# ucontrol.net
KiCad netlist of a schematic drawn in EAGLE
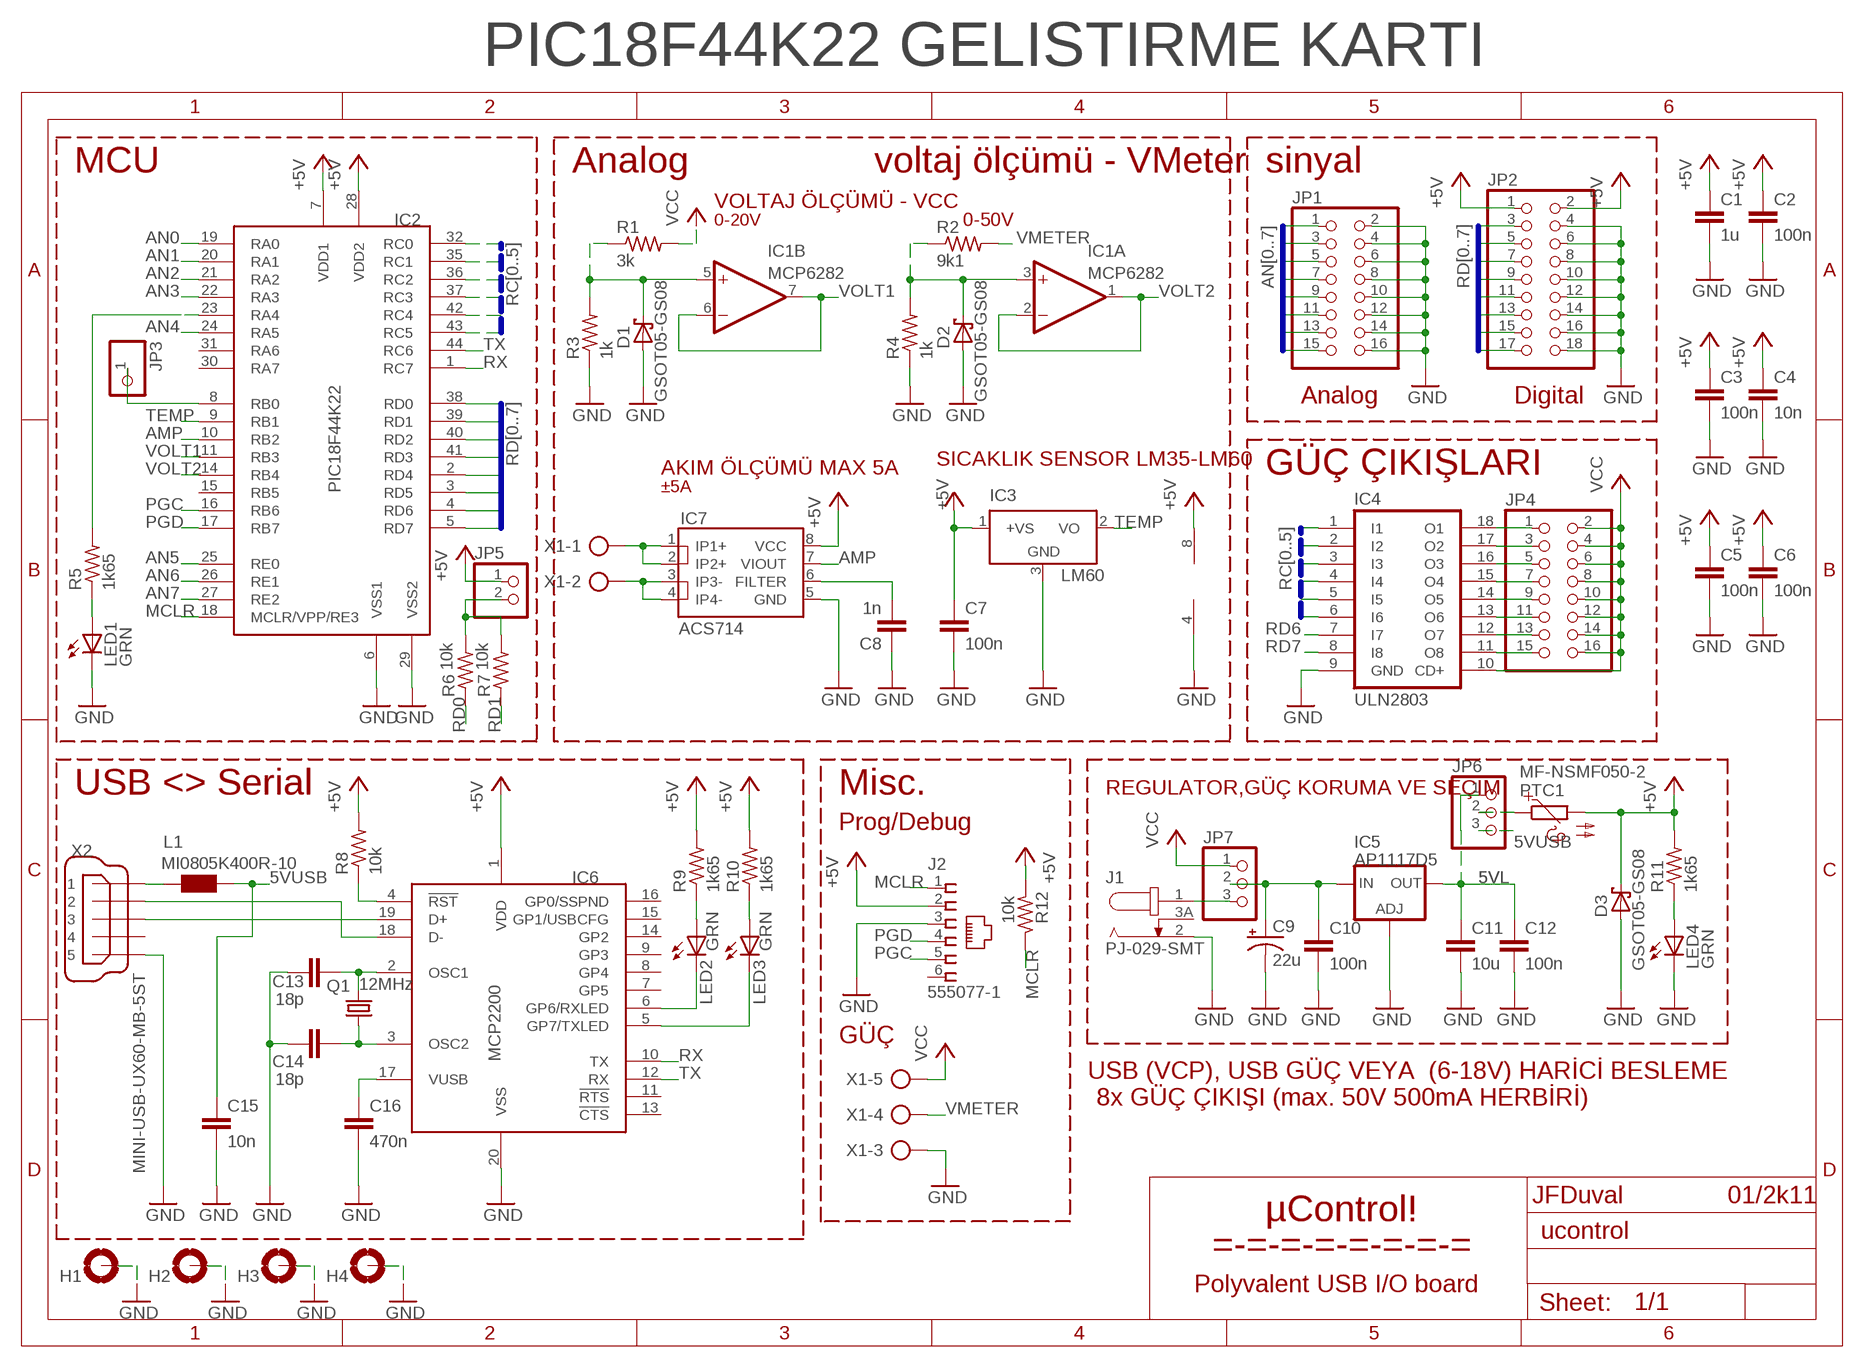
[diagram p0: schematic, sheet 1]

(export (version "E")
  (design (tool "Eeschema 10.0.6"))
  (components
    (comp (ref "C1")
      (value "1u")
      (footprint "eagle-import:C0603")
      (libsource (lib "eagle-import") (part "C-EUC0603"))
    )
    (comp (ref "C2")
      (value "100n")
      (footprint "eagle-import:C0603")
      (libsource (lib "eagle-import") (part "C-EUC0603"))
    )
    (comp (ref "C3")
      (value "100n")
      (footprint "eagle-import:C0603")
      (libsource (lib "eagle-import") (part "C-EUC0603"))
    )
    (comp (ref "C4")
      (value "10n")
      (footprint "eagle-import:C0603")
      (libsource (lib "eagle-import") (part "C-EUC0603"))
    )
    (comp (ref "C5")
      (value "100n")
      (footprint "eagle-import:C0603")
      (libsource (lib "eagle-import") (part "C-EUC0603"))
    )
    (comp (ref "C6")
      (value "100n")
      (footprint "eagle-import:C0603")
      (libsource (lib "eagle-import") (part "C-EUC0603"))
    )
    (comp (ref "C7")
      (value "100n")
      (footprint "eagle-import:C0603")
      (libsource (lib "eagle-import") (part "C-EUC0603"))
    )
    (comp (ref "C8")
      (value "1n")
      (footprint "eagle-import:C0603")
      (libsource (lib "eagle-import") (part "C-EUC0603"))
    )
    (comp (ref "C9")
      (value "22u")
      (footprint "eagle-import:153CLV-0505")
      (libsource (lib "eagle-import") (part "CPOL-US153CLV-0505"))
    )
    (comp (ref "C10")
      (value "100n")
      (footprint "eagle-import:C0603")
      (libsource (lib "eagle-import") (part "C-EUC0603"))
    )
    (comp (ref "C11")
      (value "10u")
      (footprint "eagle-import:C0805")
      (libsource (lib "eagle-import") (part "C-EUC0805"))
    )
    (comp (ref "C12")
      (value "100n")
      (footprint "eagle-import:C0603")
      (libsource (lib "eagle-import") (part "C-EUC0603"))
    )
    (comp (ref "C13")
      (value "18p")
      (footprint "eagle-import:C0603")
      (libsource (lib "eagle-import") (part "C-EUC0603"))
    )
    (comp (ref "C14")
      (value "18p")
      (footprint "eagle-import:C0603")
      (libsource (lib "eagle-import") (part "C-EUC0603"))
    )
    (comp (ref "C15")
      (value "10n")
      (footprint "eagle-import:C0603")
      (libsource (lib "eagle-import") (part "C-EUC0603"))
    )
    (comp (ref "C16")
      (value "470n")
      (footprint "eagle-import:C0603")
      (libsource (lib "eagle-import") (part "C-EUC0603"))
    )
    (comp (ref "D1")
      (value "GSOT05-GS08")
      (footprint "eagle-import:SOT23")
      (libsource (lib "eagle-import") (part "BAS70"))
    )
    (comp (ref "D2")
      (value "GSOT05-GS08")
      (footprint "eagle-import:SOT23")
      (libsource (lib "eagle-import") (part "BAS70"))
    )
    (comp (ref "D3")
      (value "GSOT05-GS08")
      (footprint "eagle-import:SOT23")
      (libsource (lib "eagle-import") (part "BAS70"))
    )
    (comp (ref "H1")
      (value "MOUNT-PAD-ROUND3.2")
      (footprint "eagle-import:3,2-PAD")
      (libsource (lib "eagle-import") (part "MOUNT-PAD-ROUND3.2"))
    )
    (comp (ref "H2")
      (value "MOUNT-PAD-ROUND3.2")
      (footprint "eagle-import:3,2-PAD")
      (libsource (lib "eagle-import") (part "MOUNT-PAD-ROUND3.2"))
    )
    (comp (ref "H3")
      (value "MOUNT-PAD-ROUND3.2")
      (footprint "eagle-import:3,2-PAD")
      (libsource (lib "eagle-import") (part "MOUNT-PAD-ROUND3.2"))
    )
    (comp (ref "H4")
      (value "MOUNT-PAD-ROUND3.2")
      (footprint "eagle-import:3,2-PAD")
      (libsource (lib "eagle-import") (part "MOUNT-PAD-ROUND3.2"))
    )
    (comp (ref "IC1")
      (value "MCP6282")
      (footprint "eagle-import:SO08")
      (libsource (lib "eagle-import") (part "MCP602SN"))
    )
    (comp (ref "IC2")
      (value "PIC18F44K22")
      (footprint "eagle-import:TQFP44")
      (libsource (lib "eagle-import") (part "PIC18F44K22"))
    )
    (comp (ref "IC3")
      (value "LM60")
      (footprint "eagle-import:SOT23")
      (libsource (lib "eagle-import") (part "LM50"))
    )
    (comp (ref "IC4")
      (value "ULN2803")
      (footprint "eagle-import:SO18")
      (libsource (lib "eagle-import") (part "ULN2803"))
    )
    (comp (ref "IC5")
      (value "AP1117D5")
      (footprint "eagle-import:DPACK")
      (libsource (lib "eagle-import") (part "LD117A?DT33TR"))
    )
    (comp (ref "IC6")
      (value "MCP2200")
      (footprint "eagle-import:SSOP20")
      (libsource (lib "eagle-import") (part "MCP2200"))
    )
    (comp (ref "IC7")
      (value "ACS714")
      (footprint "eagle-import:SO08")
      (libsource (lib "eagle-import") (part "ACS712"))
    )
    (comp (ref "J1")
      (value "PJ-029-SMT")
      (footprint "eagle-import:SMT")
      (libsource (lib "eagle-import") (part "PJ-029-SMT"))
    )
    (comp (ref "J2")
      (value "555077-1")
      (footprint "eagle-import:555077-1")
      (libsource (lib "eagle-import") (part "555077-1"))
    )
    (comp (ref "JP1")
      (value "PINHD-2X8")
      (footprint "eagle-import:2X08")
      (libsource (lib "eagle-import") (part "PINHD-2X8"))
    )
    (comp (ref "JP2")
      (value "PINHD-2X9")
      (footprint "eagle-import:2X09")
      (libsource (lib "eagle-import") (part "PINHD-2X9"))
    )
    (comp (ref "JP3")
      (value "PINHD-1X1")
      (footprint "eagle-import:1X01")
      (libsource (lib "eagle-import") (part "PINHD-1X1"))
    )
    (comp (ref "JP4")
      (value "PINHD-2X8")
      (footprint "eagle-import:2X08")
      (libsource (lib "eagle-import") (part "PINHD-2X8"))
    )
    (comp (ref "JP5")
      (value "PINHD-1X2")
      (footprint "eagle-import:1X02")
      (libsource (lib "eagle-import") (part "PINHD-1X2"))
    )
    (comp (ref "JP6")
      (value "PINHD-1X3")
      (footprint "eagle-import:1X03")
      (libsource (lib "eagle-import") (part "PINHD-1X3"))
    )
    (comp (ref "JP7")
      (value "PINHD-1X3")
      (footprint "eagle-import:1X03")
      (libsource (lib "eagle-import") (part "PINHD-1X3"))
    )
    (comp (ref "L1")
      (value "MI0805K400R-10")
      (footprint "eagle-import:0805")
      (libsource (lib "eagle-import") (part "WE-CBF_0805"))
    )
    (comp (ref "LED1")
      (value "GRN")
      (footprint "eagle-import:CHIPLED_0603")
      (libsource (lib "eagle-import") (part "LEDCHIPLED_0603"))
    )
    (comp (ref "LED2")
      (value "GRN")
      (footprint "eagle-import:CHIPLED_0603")
      (libsource (lib "eagle-import") (part "LEDCHIPLED_0603"))
    )
    (comp (ref "LED3")
      (value "GRN")
      (footprint "eagle-import:CHIPLED_0603")
      (libsource (lib "eagle-import") (part "LEDCHIPLED_0603"))
    )
    (comp (ref "LED4")
      (value "GRN")
      (footprint "eagle-import:CHIPLED_0603")
      (libsource (lib "eagle-import") (part "LEDCHIPLED_0603"))
    )
    (comp (ref "PTC1")
      (value "MF-NSMF050-2")
      (footprint "eagle-import:1206")
      (libsource (lib "eagle-import") (part "GENERIC_1206"))
    )
    (comp (ref "Q1")
      (value "12MHz")
      (footprint "eagle-import:HC49UP")
      (libsource (lib "eagle-import") (part "CRYSTALHC49UP"))
    )
    (comp (ref "R1")
      (value "3k")
      (footprint "eagle-import:R0603")
      (libsource (lib "eagle-import") (part "R-US_R0603"))
    )
    (comp (ref "R2")
      (value "9k1")
      (footprint "eagle-import:R0603")
      (libsource (lib "eagle-import") (part "R-US_R0603"))
    )
    (comp (ref "R3")
      (value "1k")
      (footprint "eagle-import:R0603")
      (libsource (lib "eagle-import") (part "R-US_R0603"))
    )
    (comp (ref "R4")
      (value "1k")
      (footprint "eagle-import:R0603")
      (libsource (lib "eagle-import") (part "R-US_R0603"))
    )
    (comp (ref "R5")
      (value "1k65")
      (footprint "eagle-import:R0603")
      (libsource (lib "eagle-import") (part "R-US_R0603"))
    )
    (comp (ref "R6")
      (value "10k")
      (footprint "eagle-import:R0603")
      (libsource (lib "eagle-import") (part "R-US_R0603"))
    )
    (comp (ref "R7")
      (value "10k")
      (footprint "eagle-import:R0603")
      (libsource (lib "eagle-import") (part "R-US_R0603"))
    )
    (comp (ref "R8")
      (value "10k")
      (footprint "eagle-import:R0603")
      (libsource (lib "eagle-import") (part "R-US_R0603"))
    )
    (comp (ref "R9")
      (value "1k65")
      (footprint "eagle-import:R0603")
      (libsource (lib "eagle-import") (part "R-US_R0603"))
    )
    (comp (ref "R10")
      (value "1k65")
      (footprint "eagle-import:R0603")
      (libsource (lib "eagle-import") (part "R-US_R0603"))
    )
    (comp (ref "R11")
      (value "1k65")
      (footprint "eagle-import:R0603")
      (libsource (lib "eagle-import") (part "R-US_R0603"))
    )
    (comp (ref "R12")
      (value "10k")
      (footprint "eagle-import:R0603")
      (libsource (lib "eagle-import") (part "R-US_R0603"))
    )
    (comp (ref "X1")
      (value "OSTTE-5")
      (footprint "eagle-import:OSTTE-5")
      (libsource (lib "eagle-import") (part "OSTTE-5"))
    )
    (comp (ref "X2")
      (value "MINI-USB-UX60-MB-5ST")
      (footprint "eagle-import:UX60-MB-5ST")
      (libsource (lib "eagle-import") (part "MINI-USB-UX60-MB-5ST"))
    )
  )
  (nets
    (net (code "1") (name "+5V") (class "Default")
      (node (ref "C1") (pin "1") (pinfunction "1_1") (pintype "passive"))
      (node (ref "C2") (pin "1") (pinfunction "1_1") (pintype "passive"))
      (node (ref "C3") (pin "1") (pinfunction "1_1") (pintype "passive"))
      (node (ref "C4") (pin "1") (pinfunction "1_1") (pintype "passive"))
      (node (ref "C5") (pin "1") (pinfunction "1_1") (pintype "passive"))
      (node (ref "C6") (pin "1") (pinfunction "1_1") (pintype "passive"))
      (node (ref "C7") (pin "1") (pinfunction "1_1") (pintype "passive"))
      (node (ref "D3") (pin "3") (pinfunction "C_3") (pintype "passive"))
      (node (ref "IC1") (pin "8") (pinfunction "V+_8") (pintype "power_in"))
      (node (ref "IC2") (pin "28") (pinfunction "VDD2_28") (pintype "power_in"))
      (node (ref "IC2") (pin "7") (pinfunction "VDD1_7") (pintype "power_in"))
      (node (ref "IC3") (pin "1") (pinfunction "+VS_1") (pintype "input"))
      (node (ref "IC6") (pin "1") (pinfunction "VDD_1") (pintype "bidirectional"))
      (node (ref "IC7") (pin "8") (pinfunction "VCC_8") (pintype "power_in"))
      (node (ref "J2") (pin "2") (pinfunction "2_2") (pintype "passive"))
      (node (ref "JP2") (pin "1") (pinfunction "1_1") (pintype "passive"))
      (node (ref "JP2") (pin "2") (pinfunction "2_2") (pintype "passive"))
      (node (ref "JP5") (pin "1") (pinfunction "1_1") (pintype "passive"))
      (node (ref "PTC1") (pin "2") (pinfunction "2_2") (pintype "passive"))
      (node (ref "R10") (pin "2") (pinfunction "2_2") (pintype "passive"))
      (node (ref "R11") (pin "2") (pinfunction "2_2") (pintype "passive"))
      (node (ref "R12") (pin "2") (pinfunction "2_2") (pintype "passive"))
      (node (ref "R8") (pin "2") (pinfunction "2_2") (pintype "passive"))
      (node (ref "R9") (pin "2") (pinfunction "2_2") (pintype "passive"))
    )
    (net (code "2") (name "/5VL") (class "Default")
      (node (ref "C11") (pin "1") (pinfunction "1_1") (pintype "passive"))
      (node (ref "C12") (pin "1") (pinfunction "1_1") (pintype "passive"))
      (node (ref "IC5") (pin "4") (pinfunction "OUT_4") (pintype "passive"))
      (node (ref "JP6") (pin "1") (pinfunction "1_1") (pintype "passive"))
    )
    (net (code "3") (name "/5VUSB") (class "Default")
      (node (ref "C15") (pin "1") (pinfunction "1_1") (pintype "passive"))
      (node (ref "JP6") (pin "3") (pinfunction "3_3") (pintype "passive"))
      (node (ref "L1") (pin "1") (pinfunction "1_1") (pintype "passive"))
    )
    (net (code "4") (name "/AMP") (class "Default")
      (node (ref "IC2") (pin "10") (pinfunction "RB2_10") (pintype "bidirectional"))
      (node (ref "IC7") (pin "7") (pinfunction "VIOUT_7") (pintype "output"))
    )
    (net (code "5") (name "/AN0") (class "Default")
      (node (ref "IC2") (pin "19") (pinfunction "RA0_19") (pintype "bidirectional"))
      (node (ref "JP1") (pin "15") (pinfunction "15_15") (pintype "passive"))
    )
    (net (code "6") (name "/AN1") (class "Default")
      (node (ref "IC2") (pin "20") (pinfunction "RA1_20") (pintype "bidirectional"))
      (node (ref "JP1") (pin "13") (pinfunction "13_13") (pintype "passive"))
    )
    (net (code "7") (name "/AN2") (class "Default")
      (node (ref "IC2") (pin "21") (pinfunction "RA2_21") (pintype "bidirectional"))
      (node (ref "JP1") (pin "11") (pinfunction "11_11") (pintype "passive"))
    )
    (net (code "8") (name "/AN3") (class "Default")
      (node (ref "IC2") (pin "22") (pinfunction "RA3_22") (pintype "bidirectional"))
      (node (ref "JP1") (pin "9") (pinfunction "9_9") (pintype "passive"))
    )
    (net (code "9") (name "/AN4") (class "Default")
      (node (ref "IC2") (pin "24") (pinfunction "RA5_24") (pintype "bidirectional"))
      (node (ref "JP1") (pin "7") (pinfunction "7_7") (pintype "passive"))
    )
    (net (code "10") (name "/AN5") (class "Default")
      (node (ref "IC2") (pin "25") (pinfunction "RE0_25") (pintype "bidirectional"))
      (node (ref "JP1") (pin "5") (pinfunction "5_5") (pintype "passive"))
    )
    (net (code "11") (name "/AN6") (class "Default")
      (node (ref "IC2") (pin "26") (pinfunction "RE1_26") (pintype "bidirectional"))
      (node (ref "JP1") (pin "3") (pinfunction "3_3") (pintype "passive"))
    )
    (net (code "12") (name "/AN7") (class "Default")
      (node (ref "IC2") (pin "27") (pinfunction "RE2_27") (pintype "bidirectional"))
      (node (ref "JP1") (pin "1") (pinfunction "1_1") (pintype "passive"))
    )
    (net (code "14") (name "/MCLR") (class "Default")
      (node (ref "IC2") (pin "18") (pinfunction "MCLR/VPP/RE3_18") (pintype "bidirectional"))
      (node (ref "J2") (pin "1") (pinfunction "1_1") (pintype "passive"))
      (node (ref "R12") (pin "1") (pinfunction "1_1") (pintype "passive"))
    )
    (net (code "15") (name "/PGC") (class "Default")
      (node (ref "IC2") (pin "16") (pinfunction "RB6_16") (pintype "bidirectional"))
      (node (ref "J2") (pin "5") (pinfunction "5_5") (pintype "passive"))
    )
    (net (code "16") (name "/PGD") (class "Default")
      (node (ref "IC2") (pin "17") (pinfunction "RB7_17") (pintype "bidirectional"))
      (node (ref "J2") (pin "4") (pinfunction "4_4") (pintype "passive"))
    )
    (net (code "17") (name "/RC0") (class "Default")
      (node (ref "IC2") (pin "32") (pinfunction "RC0_32") (pintype "bidirectional"))
      (node (ref "IC4") (pin "6") (pinfunction "I6_6") (pintype "input"))
    )
    (net (code "18") (name "/RC1") (class "Default")
      (node (ref "IC2") (pin "35") (pinfunction "RC1_35") (pintype "bidirectional"))
      (node (ref "IC4") (pin "5") (pinfunction "I5_5") (pintype "input"))
    )
    (net (code "19") (name "/RC2") (class "Default")
      (node (ref "IC2") (pin "36") (pinfunction "RC2_36") (pintype "bidirectional"))
      (node (ref "IC4") (pin "4") (pinfunction "I4_4") (pintype "input"))
    )
    (net (code "20") (name "/RC3") (class "Default")
      (node (ref "IC2") (pin "37") (pinfunction "RC3_37") (pintype "bidirectional"))
      (node (ref "IC4") (pin "3") (pinfunction "I3_3") (pintype "input"))
    )
    (net (code "21") (name "/RC4") (class "Default")
      (node (ref "IC2") (pin "42") (pinfunction "RC4_42") (pintype "bidirectional"))
      (node (ref "IC4") (pin "2") (pinfunction "I2_2") (pintype "input"))
    )
    (net (code "22") (name "/RC5") (class "Default")
      (node (ref "IC2") (pin "43") (pinfunction "RC5_43") (pintype "bidirectional"))
      (node (ref "IC4") (pin "1") (pinfunction "I1_1") (pintype "input"))
    )
    (net (code "24") (name "/RD0") (class "Default")
      (node (ref "IC2") (pin "38") (pinfunction "RD0_38") (pintype "bidirectional"))
      (node (ref "JP2") (pin "17") (pinfunction "17_17") (pintype "passive"))
      (node (ref "R6") (pin "1") (pinfunction "1_1") (pintype "passive"))
    )
    (net (code "25") (name "/RD1") (class "Default")
      (node (ref "IC2") (pin "39") (pinfunction "RD1_39") (pintype "bidirectional"))
      (node (ref "JP2") (pin "15") (pinfunction "15_15") (pintype "passive"))
      (node (ref "R7") (pin "1") (pinfunction "1_1") (pintype "passive"))
    )
    (net (code "26") (name "/RD2") (class "Default")
      (node (ref "IC2") (pin "40") (pinfunction "RD2_40") (pintype "bidirectional"))
      (node (ref "JP2") (pin "13") (pinfunction "13_13") (pintype "passive"))
    )
    (net (code "27") (name "/RD3") (class "Default")
      (node (ref "IC2") (pin "41") (pinfunction "RD3_41") (pintype "bidirectional"))
      (node (ref "JP2") (pin "11") (pinfunction "11_11") (pintype "passive"))
    )
    (net (code "28") (name "/RD4") (class "Default")
      (node (ref "IC2") (pin "2") (pinfunction "RD4_2") (pintype "bidirectional"))
      (node (ref "JP2") (pin "9") (pinfunction "9_9") (pintype "passive"))
    )
    (net (code "29") (name "/RD5") (class "Default")
      (node (ref "IC2") (pin "3") (pinfunction "RD5_3") (pintype "bidirectional"))
      (node (ref "JP2") (pin "7") (pinfunction "7_7") (pintype "passive"))
    )
    (net (code "30") (name "/RD6") (class "Default")
      (node (ref "IC2") (pin "4") (pinfunction "RD6_4") (pintype "bidirectional"))
      (node (ref "IC4") (pin "7") (pinfunction "I7_7") (pintype "input"))
      (node (ref "JP2") (pin "5") (pinfunction "5_5") (pintype "passive"))
    )
    (net (code "31") (name "/RD7") (class "Default")
      (node (ref "IC2") (pin "5") (pinfunction "RD7_5") (pintype "bidirectional"))
      (node (ref "IC4") (pin "8") (pinfunction "I8_8") (pintype "input"))
      (node (ref "JP2") (pin "3") (pinfunction "3_3") (pintype "passive"))
    )
    (net (code "33") (name "/RX") (class "Default")
      (node (ref "IC2") (pin "1") (pinfunction "RC7_1") (pintype "bidirectional"))
      (node (ref "IC6") (pin "10") (pinfunction "TX_10") (pintype "bidirectional"))
    )
    (net (code "34") (name "/TEMP") (class "Default")
      (node (ref "IC2") (pin "9") (pinfunction "RB1_9") (pintype "bidirectional"))
      (node (ref "IC3") (pin "2") (pinfunction "VO_2") (pintype "input"))
    )
    (net (code "35") (name "/TX") (class "Default")
      (node (ref "IC2") (pin "44") (pinfunction "RC6_44") (pintype "bidirectional"))
      (node (ref "IC6") (pin "12") (pinfunction "RX_12") (pintype "bidirectional"))
    )
    (net (code "36") (name "/VMETER") (class "Default")
      (node (ref "R2") (pin "2") (pinfunction "2_2") (pintype "passive"))
      (node (ref "X1") (pin "4") (pinfunction "KL_4") (pintype "passive"))
    )
    (net (code "37") (name "/VOLT1") (class "Default")
      (node (ref "IC1") (pin "6") (pinfunction "-IN_6") (pintype "input"))
      (node (ref "IC1") (pin "7") (pinfunction "OUT_7") (pintype "output"))
      (node (ref "IC2") (pin "11") (pinfunction "RB3_11") (pintype "bidirectional"))
    )
    (net (code "38") (name "/VOLT2") (class "Default")
      (node (ref "IC1") (pin "1") (pinfunction "OUT_1") (pintype "output"))
      (node (ref "IC1") (pin "2") (pinfunction "-IN_2") (pintype "input"))
      (node (ref "IC2") (pin "14") (pinfunction "RB4_14") (pintype "bidirectional"))
    )
    (net (code "39") (name "GND") (class "Default")
      (node (ref "C1") (pin "2") (pinfunction "2_2") (pintype "passive"))
      (node (ref "C10") (pin "2") (pinfunction "2_2") (pintype "passive"))
      (node (ref "C11") (pin "2") (pinfunction "2_2") (pintype "passive"))
      (node (ref "C12") (pin "2") (pinfunction "2_2") (pintype "passive"))
      (node (ref "C13") (pin "1") (pinfunction "1_1") (pintype "passive"))
      (node (ref "C14") (pin "1") (pinfunction "1_1") (pintype "passive"))
      (node (ref "C15") (pin "2") (pinfunction "2_2") (pintype "passive"))
      (node (ref "C16") (pin "2") (pinfunction "2_2") (pintype "passive"))
      (node (ref "C2") (pin "2") (pinfunction "2_2") (pintype "passive"))
      (node (ref "C3") (pin "2") (pinfunction "2_2") (pintype "passive"))
      (node (ref "C4") (pin "2") (pinfunction "2_2") (pintype "passive"))
      (node (ref "C5") (pin "2") (pinfunction "2_2") (pintype "passive"))
      (node (ref "C6") (pin "2") (pinfunction "2_2") (pintype "passive"))
      (node (ref "C7") (pin "2") (pinfunction "2_2") (pintype "passive"))
      (node (ref "C8") (pin "1") (pinfunction "1_1") (pintype "passive"))
      (node (ref "C9") (pin "-") (pinfunction "-_-") (pintype "passive"))
      (node (ref "D1") (pin "1") (pinfunction "A_1") (pintype "passive"))
      (node (ref "D2") (pin "1") (pinfunction "A_1") (pintype "passive"))
      (node (ref "D3") (pin "1") (pinfunction "A_1") (pintype "passive"))
      (node (ref "H1") (pin "B3,2") (pinfunction "MOUNT_B3,2") (pintype "passive"))
      (node (ref "H2") (pin "B3,2") (pinfunction "MOUNT_B3,2") (pintype "passive"))
      (node (ref "H3") (pin "B3,2") (pinfunction "MOUNT_B3,2") (pintype "passive"))
      (node (ref "H4") (pin "B3,2") (pinfunction "MOUNT_B3,2") (pintype "passive"))
      (node (ref "IC1") (pin "4") (pinfunction "V-_4") (pintype "power_in"))
      (node (ref "IC2") (pin "29") (pinfunction "VSS2_29") (pintype "power_in"))
      (node (ref "IC2") (pin "6") (pinfunction "VSS1_6") (pintype "power_in"))
      (node (ref "IC3") (pin "3") (pinfunction "GND_3") (pintype "power_in"))
      (node (ref "IC4") (pin "9") (pinfunction "GND_9") (pintype "power_in"))
      (node (ref "IC5") (pin "1") (pinfunction "ADJ_1") (pintype "input"))
      (node (ref "IC6") (pin "20") (pinfunction "VSS_20") (pintype "bidirectional"))
      (node (ref "IC7") (pin "5") (pinfunction "GND_5") (pintype "power_in"))
      (node (ref "J1") (pin "2") (pinfunction "1_2") (pintype "passive"))
      (node (ref "J2") (pin "3") (pinfunction "3_3") (pintype "passive"))
      (node (ref "JP1") (pin "10") (pinfunction "10_10") (pintype "passive"))
      (node (ref "JP1") (pin "12") (pinfunction "12_12") (pintype "passive"))
      (node (ref "JP1") (pin "14") (pinfunction "14_14") (pintype "passive"))
      (node (ref "JP1") (pin "16") (pinfunction "16_16") (pintype "passive"))
      (node (ref "JP1") (pin "2") (pinfunction "2_2") (pintype "passive"))
      (node (ref "JP1") (pin "4") (pinfunction "4_4") (pintype "passive"))
      (node (ref "JP1") (pin "6") (pinfunction "6_6") (pintype "passive"))
      (node (ref "JP1") (pin "8") (pinfunction "8_8") (pintype "passive"))
      (node (ref "JP2") (pin "10") (pinfunction "10_10") (pintype "passive"))
      (node (ref "JP2") (pin "12") (pinfunction "12_12") (pintype "passive"))
      (node (ref "JP2") (pin "14") (pinfunction "14_14") (pintype "passive"))
      (node (ref "JP2") (pin "16") (pinfunction "16_16") (pintype "passive"))
      (node (ref "JP2") (pin "18") (pinfunction "18_18") (pintype "passive"))
      (node (ref "JP2") (pin "4") (pinfunction "4_4") (pintype "passive"))
      (node (ref "JP2") (pin "6") (pinfunction "6_6") (pintype "passive"))
      (node (ref "JP2") (pin "8") (pinfunction "8_8") (pintype "passive"))
      (node (ref "LED1") (pin "C") (pinfunction "C_C") (pintype "passive"))
      (node (ref "LED4") (pin "C") (pinfunction "C_C") (pintype "passive"))
      (node (ref "R3") (pin "1") (pinfunction "1_1") (pintype "passive"))
      (node (ref "R4") (pin "1") (pinfunction "1_1") (pintype "passive"))
      (node (ref "X1") (pin "3") (pinfunction "KL_3") (pintype "passive"))
      (node (ref "X2") (pin "5") (pinfunction "5_5") (pintype "input"))
    )
    (net (code "40") (name "Net-(D1-C)") (class "Default")
      (node (ref "D1") (pin "3") (pinfunction "C_3") (pintype "passive"))
      (node (ref "IC1") (pin "5") (pinfunction "+IN_5") (pintype "input"))
      (node (ref "R1") (pin "1") (pinfunction "1_1") (pintype "passive"))
      (node (ref "R3") (pin "2") (pinfunction "2_2") (pintype "passive"))
    )
    (net (code "41") (name "Net-(D2-C)") (class "Default")
      (node (ref "D2") (pin "3") (pinfunction "C_3") (pintype "passive"))
      (node (ref "IC1") (pin "3") (pinfunction "+IN_3") (pintype "input"))
      (node (ref "R2") (pin "1") (pinfunction "1_1") (pintype "passive"))
      (node (ref "R4") (pin "2") (pinfunction "2_2") (pintype "passive"))
    )
    (net (code "42") (name "Net-(IC2-RA4)") (class "Default")
      (node (ref "IC2") (pin "23") (pinfunction "RA4_23") (pintype "bidirectional"))
      (node (ref "R5") (pin "2") (pinfunction "2_2") (pintype "passive"))
    )
    (net (code "43") (name "Net-(IC2-RB0)") (class "Default")
      (node (ref "IC2") (pin "8") (pinfunction "RB0_8") (pintype "bidirectional"))
      (node (ref "JP3") (pin "1") (pinfunction "1_1") (pintype "passive"))
    )
    (net (code "44") (name "Net-(IC4-O1)") (class "Default")
      (node (ref "IC4") (pin "18") (pinfunction "O1_18") (pintype "open_collector"))
      (node (ref "JP4") (pin "1") (pinfunction "1_1") (pintype "passive"))
    )
    (net (code "45") (name "Net-(IC4-O2)") (class "Default")
      (node (ref "IC4") (pin "17") (pinfunction "O2_17") (pintype "open_collector"))
      (node (ref "JP4") (pin "3") (pinfunction "3_3") (pintype "passive"))
    )
    (net (code "46") (name "Net-(IC4-O3)") (class "Default")
      (node (ref "IC4") (pin "16") (pinfunction "O3_16") (pintype "open_collector"))
      (node (ref "JP4") (pin "5") (pinfunction "5_5") (pintype "passive"))
    )
    (net (code "47") (name "Net-(IC4-O4)") (class "Default")
      (node (ref "IC4") (pin "15") (pinfunction "O4_15") (pintype "open_collector"))
      (node (ref "JP4") (pin "7") (pinfunction "7_7") (pintype "passive"))
    )
    (net (code "48") (name "Net-(IC4-O5)") (class "Default")
      (node (ref "IC4") (pin "14") (pinfunction "O5_14") (pintype "open_collector"))
      (node (ref "JP4") (pin "9") (pinfunction "9_9") (pintype "passive"))
    )
    (net (code "49") (name "Net-(IC4-O6)") (class "Default")
      (node (ref "IC4") (pin "13") (pinfunction "O6_13") (pintype "open_collector"))
      (node (ref "JP4") (pin "11") (pinfunction "11_11") (pintype "passive"))
    )
    (net (code "50") (name "Net-(IC4-O7)") (class "Default")
      (node (ref "IC4") (pin "12") (pinfunction "O7_12") (pintype "open_collector"))
      (node (ref "JP4") (pin "13") (pinfunction "13_13") (pintype "passive"))
    )
    (net (code "51") (name "Net-(IC4-O8)") (class "Default")
      (node (ref "IC4") (pin "11") (pinfunction "O8_11") (pintype "open_collector"))
      (node (ref "JP4") (pin "15") (pinfunction "15_15") (pintype "passive"))
    )
    (net (code "52") (name "Net-(IC5-IN)") (class "Default")
      (node (ref "C10") (pin "1") (pinfunction "1_1") (pintype "passive"))
      (node (ref "C9") (pin "+") (pinfunction "+_+") (pintype "passive"))
      (node (ref "IC5") (pin "3") (pinfunction "IN_3") (pintype "input"))
      (node (ref "JP7") (pin "2") (pinfunction "2_2") (pintype "passive"))
    )
    (net (code "53") (name "Net-(IC6-D+)") (class "Default")
      (node (ref "IC6") (pin "19") (pinfunction "D+_19") (pintype "bidirectional"))
      (node (ref "X2") (pin "3") (pinfunction "3_3") (pintype "input"))
    )
    (net (code "54") (name "Net-(IC6-D-)") (class "Default")
      (node (ref "IC6") (pin "18") (pinfunction "D-_18") (pintype "bidirectional"))
      (node (ref "X2") (pin "2") (pinfunction "2_2") (pintype "input"))
    )
    (net (code "55") (name "Net-(IC6-GP6{slash}RXLED)") (class "Default")
      (node (ref "IC6") (pin "6") (pinfunction "GP6/RXLED_6") (pintype "bidirectional"))
      (node (ref "LED2") (pin "C") (pinfunction "C_C") (pintype "passive"))
    )
    (net (code "56") (name "Net-(IC6-GP7{slash}TXLED)") (class "Default")
      (node (ref "IC6") (pin "5") (pinfunction "GP7/TXLED_5") (pintype "bidirectional"))
      (node (ref "LED3") (pin "C") (pinfunction "C_C") (pintype "passive"))
    )
    (net (code "57") (name "Net-(IC6-OSC1)") (class "Default")
      (node (ref "C13") (pin "2") (pinfunction "2_2") (pintype "passive"))
      (node (ref "IC6") (pin "2") (pinfunction "OSC1_2") (pintype "bidirectional"))
      (node (ref "Q1") (pin "2") (pinfunction "2_2") (pintype "passive"))
    )
    (net (code "58") (name "Net-(IC6-OSC2)") (class "Default")
      (node (ref "C14") (pin "2") (pinfunction "2_2") (pintype "passive"))
      (node (ref "IC6") (pin "3") (pinfunction "OSC2_3") (pintype "bidirectional"))
      (node (ref "Q1") (pin "1") (pinfunction "1_1") (pintype "passive"))
    )
    (net (code "59") (name "Net-(IC6-VUSB)") (class "Default")
      (node (ref "C16") (pin "1") (pinfunction "1_1") (pintype "passive"))
      (node (ref "IC6") (pin "17") (pinfunction "VUSB_17") (pintype "bidirectional"))
    )
    (net (code "60") (name "Net-(IC6-~{RST})") (class "Default")
      (node (ref "IC6") (pin "4") (pinfunction "~{RST}_4") (pintype "bidirectional"))
      (node (ref "R8") (pin "1") (pinfunction "1_1") (pintype "passive"))
    )
    (net (code "61") (name "Net-(IC7-FILTER)") (class "Default")
      (node (ref "C8") (pin "2") (pinfunction "2_2") (pintype "passive"))
      (node (ref "IC7") (pin "6") (pinfunction "FILTER_6") (pintype "passive"))
    )
    (net (code "62") (name "Net-(IC7-IP1+)") (class "Default")
      (node (ref "IC7") (pin "1") (pinfunction "IP1+_1") (pintype "bidirectional"))
      (node (ref "IC7") (pin "2") (pinfunction "IP2+_2") (pintype "bidirectional"))
      (node (ref "X1") (pin "1") (pinfunction "KL_1") (pintype "passive"))
    )
    (net (code "63") (name "Net-(IC7-IP3-)") (class "Default")
      (node (ref "IC7") (pin "3") (pinfunction "IP3-_3") (pintype "bidirectional"))
      (node (ref "IC7") (pin "4") (pinfunction "IP4-_4") (pintype "bidirectional"))
      (node (ref "X1") (pin "2") (pinfunction "KL_2") (pintype "passive"))
    )
    (net (code "64") (name "Net-(J1-3)") (class "Default")
      (node (ref "J1") (pin "1") (pinfunction "3_1") (pintype "passive"))
      (node (ref "JP7") (pin "3") (pinfunction "3_3") (pintype "passive"))
    )
    (net (code "65") (name "Net-(JP5-Pad2)") (class "Default")
      (node (ref "JP5") (pin "2") (pinfunction "2_2") (pintype "passive"))
      (node (ref "R6") (pin "2") (pinfunction "2_2") (pintype "passive"))
      (node (ref "R7") (pin "2") (pinfunction "2_2") (pintype "passive"))
    )
    (net (code "66") (name "Net-(JP6-Pad2)") (class "Default")
      (node (ref "JP6") (pin "2") (pinfunction "2_2") (pintype "passive"))
      (node (ref "PTC1") (pin "1") (pinfunction "1_1") (pintype "passive"))
    )
    (net (code "67") (name "Net-(L1-Pad2)") (class "Default")
      (node (ref "L1") (pin "2") (pinfunction "2_2") (pintype "passive"))
      (node (ref "X2") (pin "1") (pinfunction "1_1") (pintype "input"))
    )
    (net (code "68") (name "Net-(LED1-PadA)") (class "Default")
      (node (ref "LED1") (pin "A") (pinfunction "A_A") (pintype "passive"))
      (node (ref "R5") (pin "1") (pinfunction "1_1") (pintype "passive"))
    )
    (net (code "69") (name "Net-(LED2-PadA)") (class "Default")
      (node (ref "LED2") (pin "A") (pinfunction "A_A") (pintype "passive"))
      (node (ref "R9") (pin "1") (pinfunction "1_1") (pintype "passive"))
    )
    (net (code "70") (name "Net-(LED3-PadA)") (class "Default")
      (node (ref "LED3") (pin "A") (pinfunction "A_A") (pintype "passive"))
      (node (ref "R10") (pin "1") (pinfunction "1_1") (pintype "passive"))
    )
    (net (code "71") (name "Net-(LED4-PadA)") (class "Default")
      (node (ref "LED4") (pin "A") (pinfunction "A_A") (pintype "passive"))
      (node (ref "R11") (pin "1") (pinfunction "1_1") (pintype "passive"))
    )
    (net (code "72") (name "VCC") (class "Default")
      (node (ref "IC4") (pin "10") (pinfunction "CD+_10") (pintype "passive"))
      (node (ref "JP4") (pin "10") (pinfunction "10_10") (pintype "passive"))
      (node (ref "JP4") (pin "12") (pinfunction "12_12") (pintype "passive"))
      (node (ref "JP4") (pin "14") (pinfunction "14_14") (pintype "passive"))
      (node (ref "JP4") (pin "16") (pinfunction "16_16") (pintype "passive"))
      (node (ref "JP4") (pin "2") (pinfunction "2_2") (pintype "passive"))
      (node (ref "JP4") (pin "4") (pinfunction "4_4") (pintype "passive"))
      (node (ref "JP4") (pin "6") (pinfunction "6_6") (pintype "passive"))
      (node (ref "JP4") (pin "8") (pinfunction "8_8") (pintype "passive"))
      (node (ref "JP7") (pin "1") (pinfunction "1_1") (pintype "passive"))
      (node (ref "R1") (pin "2") (pinfunction "2_2") (pintype "passive"))
      (node (ref "X1") (pin "5") (pinfunction "KL_5") (pintype "passive"))
    )
    (net (code "73") (name "unconnected-(IC2-RA6-Pad31)") (class "Default")
      (node (ref "IC2") (pin "31") (pinfunction "RA6_31") (pintype "bidirectional"))
    )
    (net (code "74") (name "unconnected-(IC2-RA7-Pad30)") (class "Default")
      (node (ref "IC2") (pin "30") (pinfunction "RA7_30") (pintype "bidirectional"))
    )
    (net (code "75") (name "unconnected-(IC2-RB5-Pad15)") (class "Default")
      (node (ref "IC2") (pin "15") (pinfunction "RB5_15") (pintype "bidirectional"))
    )
    (net (code "76") (name "unconnected-(IC6-GP0{slash}SSPND-Pad16)") (class "Default")
      (node (ref "IC6") (pin "16") (pinfunction "GP0/SSPND_16") (pintype "bidirectional"))
    )
    (net (code "77") (name "unconnected-(IC6-GP1{slash}USBCFG-Pad15)") (class "Default")
      (node (ref "IC6") (pin "15") (pinfunction "GP1/USBCFG_15") (pintype "bidirectional"))
    )
    (net (code "78") (name "unconnected-(IC6-GP2-Pad14)") (class "Default")
      (node (ref "IC6") (pin "14") (pinfunction "GP2_14") (pintype "bidirectional"))
    )
    (net (code "79") (name "unconnected-(IC6-GP3-Pad9)") (class "Default")
      (node (ref "IC6") (pin "9") (pinfunction "GP3_9") (pintype "bidirectional"))
    )
    (net (code "80") (name "unconnected-(IC6-GP4-Pad8)") (class "Default")
      (node (ref "IC6") (pin "8") (pinfunction "GP4_8") (pintype "bidirectional"))
    )
    (net (code "81") (name "unconnected-(IC6-GP5-Pad7)") (class "Default")
      (node (ref "IC6") (pin "7") (pinfunction "GP5_7") (pintype "bidirectional"))
    )
    (net (code "82") (name "unconnected-(IC6-~{CTS}-Pad13)") (class "Default")
      (node (ref "IC6") (pin "13") (pinfunction "~{CTS}_13") (pintype "bidirectional"))
    )
    (net (code "83") (name "unconnected-(IC6-~{RTS}-Pad11)") (class "Default")
      (node (ref "IC6") (pin "11") (pinfunction "~{RTS}_11") (pintype "bidirectional"))
    )
    (net (code "84") (name "unconnected-(J1-2-Pad3A)") (class "Default")
      (node (ref "J1") (pin "3A") (pinfunction "2_3A") (pintype "passive"))
    )
    (net (code "85") (name "unconnected-(J2-Pad6)") (class "Default")
      (node (ref "J2") (pin "6") (pinfunction "6_6") (pintype "passive"))
    )
    (net (code "86") (name "unconnected-(X2-Pad4)") (class "Default")
      (node (ref "X2") (pin "4") (pinfunction "4_4") (pintype "input"))
    )
  )
)
